# INA219_CH6.net
KiCad netlist of a schematic drawn in Altium Designer
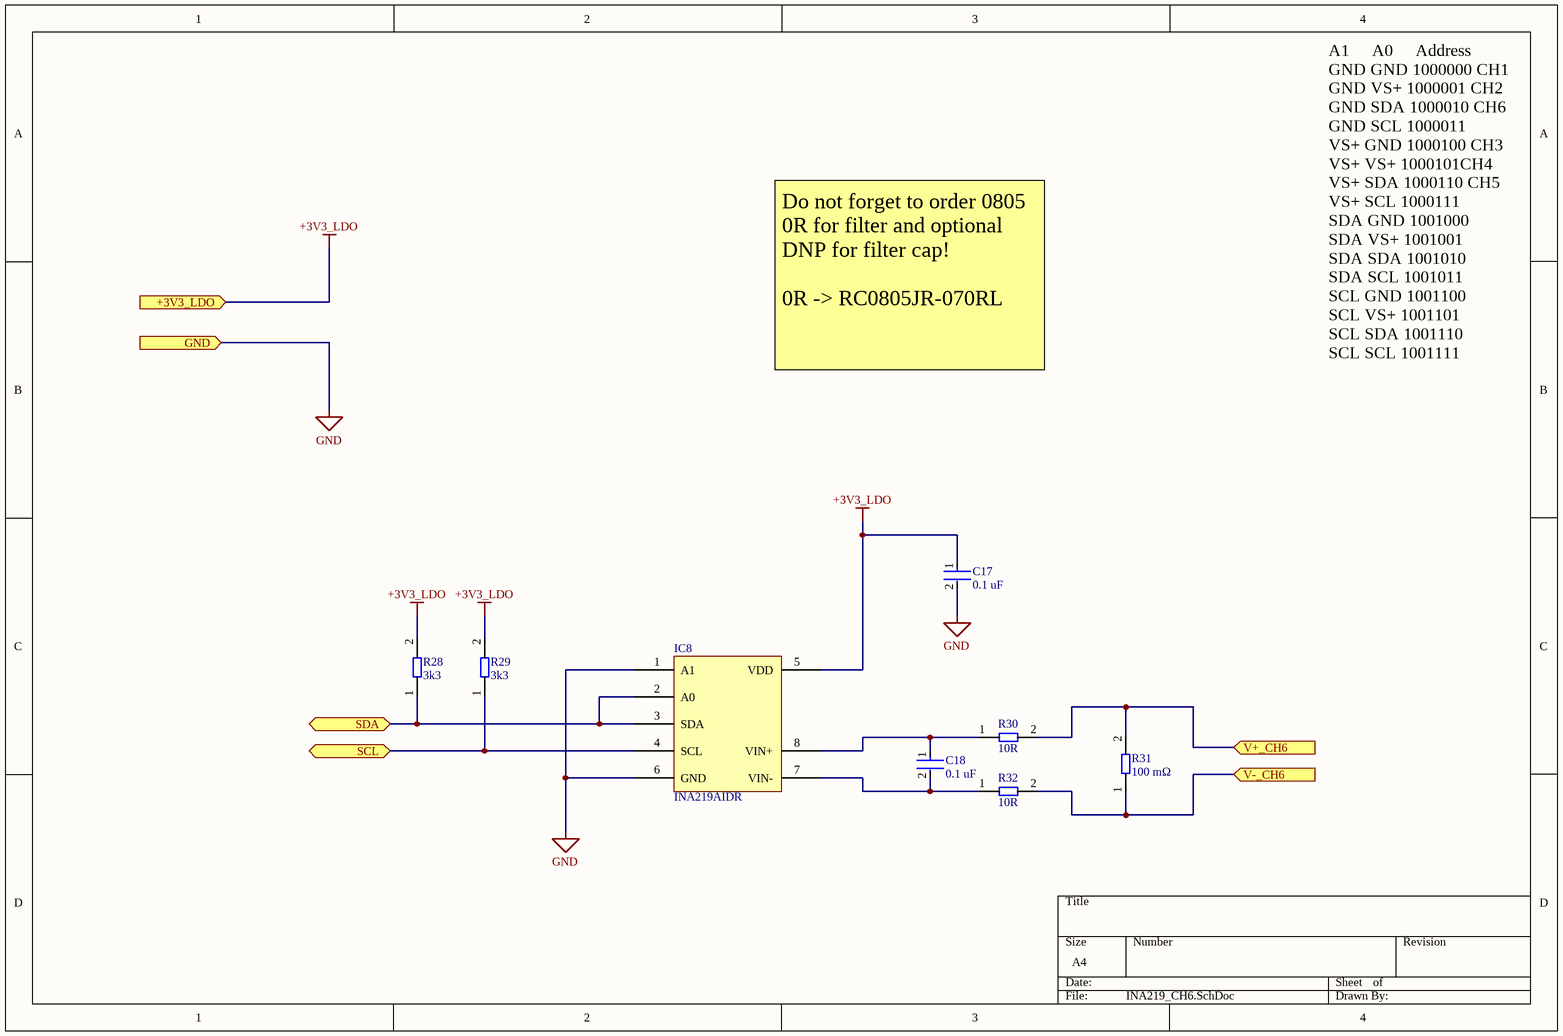
[diagram p0: INA219_CH6.SchDoc]

(export (version "E")
  (design (tool "Eeschema 10.0.6"))
  (components
    (comp (ref "C17")
      (value "0.1 uF")
      (footprint "FP-C0805C-DN-MFG")
      (description "C0805 0.10 μF X7R 30ppm/°C 20.00% 50 V C0805C104M5RAC")
      (fields
        (field (name "MANUFACTURER PART NUMBER") "C0805C104M5RAC")
        (field (name "MANUFACTURER") "KEMET")
      )
      (libsource (lib "Altium Content Vault") (part "b4654b650e69147ec39a6b967a45e02"))
    )
    (comp (ref "C18")
      (value "0.1 uF")
      (footprint "FP-C0805C-DN-MFG")
      (description "C0805 0.10 μF X7R 30ppm/°C 20.00% 50 V C0805C104M5RAC")
      (fields
        (field (name "MANUFACTURER PART NUMBER") "C0805C104M5RAC")
        (field (name "MANUFACTURER") "KEMET")
      )
      (libsource (lib "Altium Content Vault") (part "b4654b650e69147ec39a6b967a45e02"))
    )
    (comp (ref "IC8")
      (value "INA219AIDR")
      (footprint "INA219AIDR")
      (description "Current & Power Monitors & Regulators Zero-Drift,Bi-Dir Crnt/Pwr Monitor")
      (libsource (lib "Callisto Control Board") (part "INA219AIDR"))
    )
    (comp (ref "R28")
      (value "3k3")
      (footprint "0805 Resistor - IPC A")
      (description "Thick Film Resistors - SMD 3.3 kOhms 125 mW 0805 1%\r\nRE0805FRE073K3L")
      (libsource (lib "Callisto Control Board") (part "RE0805FRE073K3L"))
    )
    (comp (ref "R29")
      (value "3k3")
      (footprint "0805 Resistor - IPC A")
      (description "Thick Film Resistors - SMD 3.3 kOhms 125 mW 0805 1%\r\nRE0805FRE073K3L")
      (libsource (lib "Callisto Control Board") (part "RE0805FRE073K3L"))
    )
    (comp (ref "R30")
      (value "10R")
      (footprint "0805 Resistor - IPC A")
      (description "Thick Film Resistors - SMD 10 Ohms 125 mW 0805 1%\r\nRC0805FR-0710RL")
      (libsource (lib "Callisto Control Board") (part "RC0805FR-0710RL"))
    )
    (comp (ref "R31")
      (value "100 mΩ")
      (footprint "PE2512FKM070R1L")
      (description "Current Sense Resistors - SMD 100 mOhms 1 Watt 1 % 75 ppm/C AEC-Q200\r\nPE2512FKM070R1L")
      (libsource (lib "Callisto Control Board") (part "PE2512FKM070R1L"))
    )
    (comp (ref "R32")
      (value "10R")
      (footprint "0805 Resistor - IPC A")
      (description "Thick Film Resistors - SMD 10 Ohms 125 mW 0805 1%\r\nRC0805FR-0710RL")
      (libsource (lib "Callisto Control Board") (part "RC0805FR-0710RL"))
    )
  )
  (nets
    (net (code "1") (name "+3V3_LDO") (class "Default")
      (node (ref "C17") (pin "1") (pinfunction "1_1") (pintype "passive"))
      (node (ref "IC8") (pin "5") (pinfunction "VDD_5") (pintype "passive"))
      (node (ref "R28") (pin "2") (pintype "passive"))
      (node (ref "R29") (pin "2") (pintype "passive"))
    )
    (net (code "2") (name "/SCL") (class "Default")
      (node (ref "IC8") (pin "4") (pinfunction "SCL_4") (pintype "passive"))
      (node (ref "R29") (pin "1") (pintype "passive"))
    )
    (net (code "3") (name "/SDA") (class "Default")
      (node (ref "IC8") (pin "2") (pinfunction "A0_2") (pintype "passive"))
      (node (ref "IC8") (pin "3") (pinfunction "SDA_3") (pintype "passive"))
      (node (ref "R28") (pin "1") (pintype "passive"))
    )
    (net (code "4") (name "/V+_CH6") (class "Default")
      (node (ref "R30") (pin "2") (pintype "passive"))
      (node (ref "R31") (pin "2") (pintype "passive"))
    )
    (net (code "5") (name "/V-_CH6") (class "Default")
      (node (ref "R31") (pin "1") (pintype "passive"))
      (node (ref "R32") (pin "2") (pintype "passive"))
    )
    (net (code "6") (name "GND") (class "Default")
      (node (ref "C17") (pin "2") (pinfunction "2_2") (pintype "passive"))
      (node (ref "IC8") (pin "1") (pinfunction "A1_1") (pintype "passive"))
      (node (ref "IC8") (pin "6") (pinfunction "GND_6") (pintype "passive"))
    )
    (net (code "7") (name "Net-(IC8-VIN+)") (class "Default")
      (node (ref "C18") (pin "1") (pinfunction "1_1") (pintype "passive"))
      (node (ref "IC8") (pin "8") (pinfunction "VIN+_8") (pintype "passive"))
      (node (ref "R30") (pin "1") (pintype "passive"))
    )
    (net (code "8") (name "Net-(IC8-VIN-)") (class "Default")
      (node (ref "C18") (pin "2") (pinfunction "2_2") (pintype "passive"))
      (node (ref "IC8") (pin "7") (pinfunction "VIN-_7") (pintype "passive"))
      (node (ref "R32") (pin "1") (pintype "passive"))
    )
  )
)
